# Connectors.net
KiCad netlist of a schematic drawn in Altium Designer
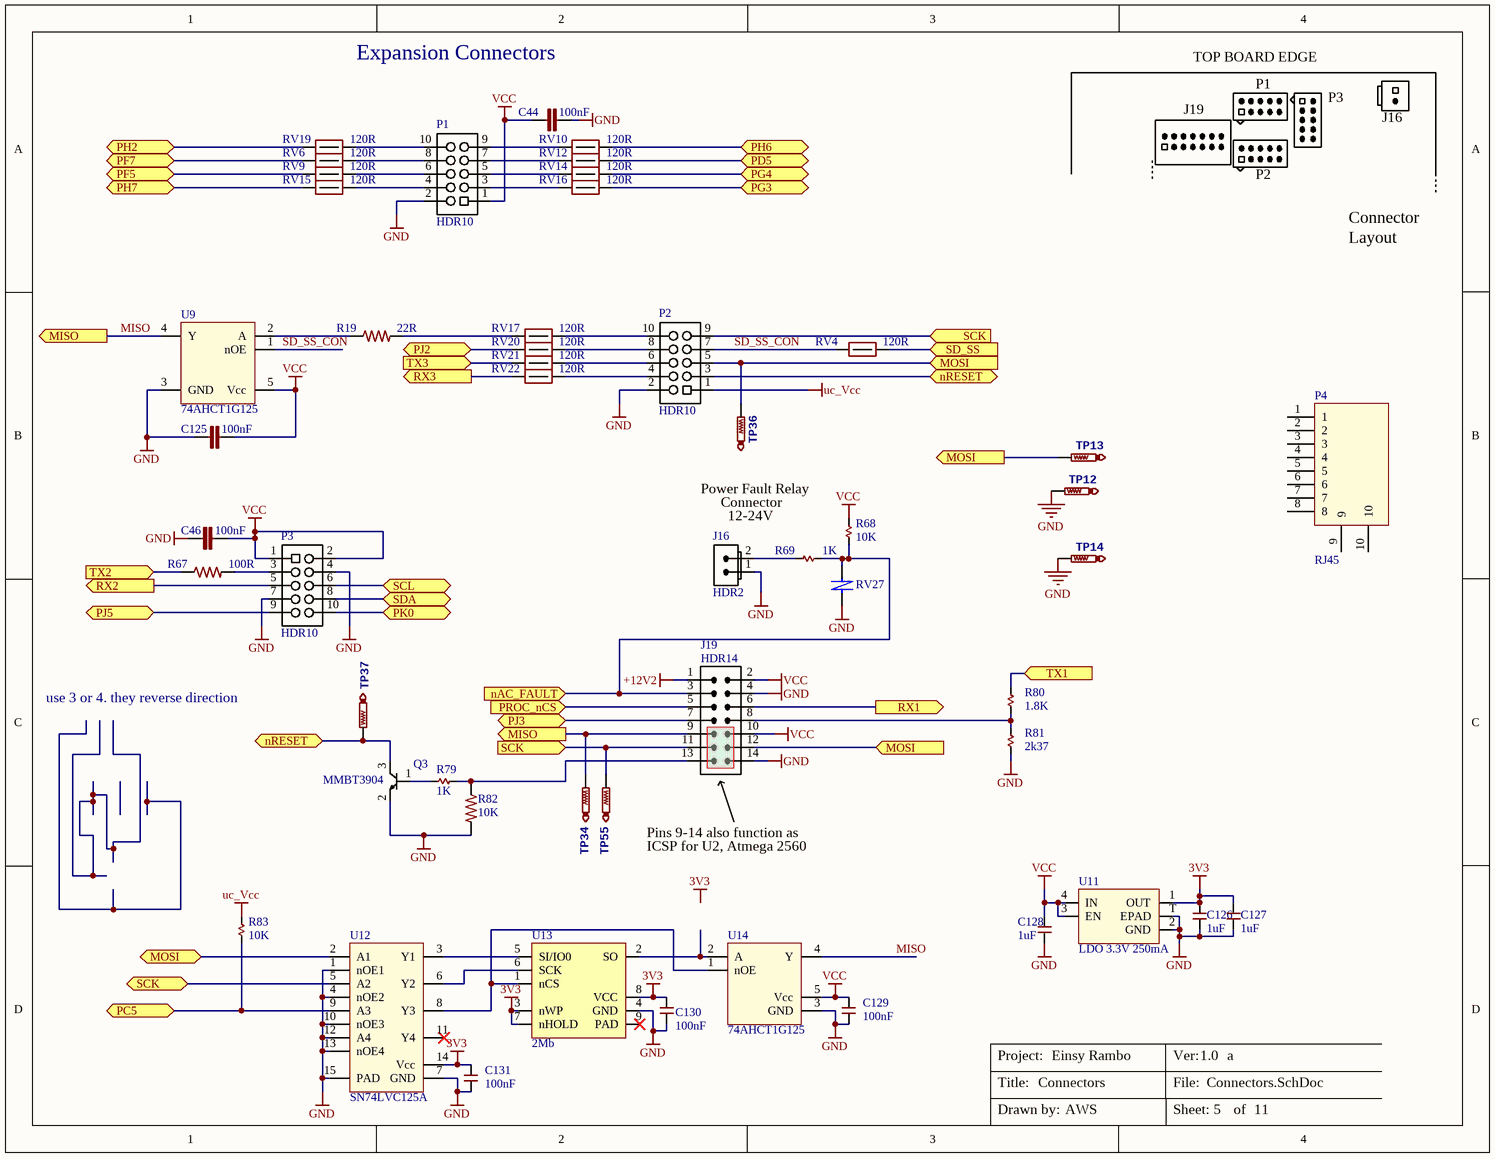
[diagram p0: Connectors.SchDoc]

(export (version "E")
  (design (tool "Eeschema 10.0.6"))
  (components
    (comp (ref "C44")
      (value "100nF")
      (footprint "C0402")
      (description "CAP CER 0402 100nF 16V 10% X7R")
      (fields (field (name "MANUFACTURER") "Murata") (field (name "TOLERANCE") "+/- 10%"))
      (libsource (lib "3Delight") (part "GRM155R71C104KA88D"))
    )
    (comp (ref "C46")
      (value "100nF")
      (footprint "C0402")
      (description "CAP CER 0402 100nF 16V 10% X7R")
      (fields (field (name "MANUFACTURER") "Murata") (field (name "TOLERANCE") "+/- 10%"))
      (libsource (lib "3Delight") (part "GRM155R71C104KA88D"))
    )
    (comp (ref "C125")
      (value "100nF")
      (footprint "C0402")
      (description "CAP CER 0402 100nF 16V 10% X7R")
      (fields (field (name "MANUFACTURER") "Murata") (field (name "TOLERANCE") "+/- 10%"))
      (libsource (lib "3Delight") (part "GRM155R71C104KA88D"))
    )
    (comp (ref "C126")
      (value "1uF")
      (footprint "C0402")
      (description "CAP CER 0402 1uF 6.3V 10% X5R")
      (fields (field (name "MANUFACTURER") "Murata") (field (name "PART") "1uF 6.3V X5R 0402"))
      (libsource (lib "Capacitors") (part "1uF 0402 6.3V X5R"))
    )
    (comp (ref "C127")
      (value "1uF")
      (footprint "C0402")
      (description "CAP CER 0402 1uF 6.3V 10% X5R")
      (fields (field (name "MANUFACTURER") "Murata") (field (name "PART") "1uF 6.3V X5R 0402"))
      (libsource (lib "Capacitors") (part "1uF 0402 6.3V X5R"))
    )
    (comp (ref "C128")
      (value "1uF")
      (footprint "C0402")
      (description "CAP CER 0402 1uF 6.3V 10% X5R")
      (fields (field (name "MANUFACTURER") "Murata") (field (name "PART") "1uF 6.3V X5R 0402"))
      (libsource (lib "Capacitors") (part "1uF 0402 6.3V X5R"))
    )
    (comp (ref "C129")
      (value "100nF")
      (footprint "C0402")
      (description "CAP CER 0402 100nF 16V 10% X7R")
      (fields (field (name "MANUFACTURER") "Murata") (field (name "PART") "0.1uF 16V X7R 0402"))
      (libsource (lib "Capacitors") (part "100nF 0402 16V X7R"))
    )
    (comp (ref "C130")
      (value "100nF")
      (footprint "C0402")
      (description "CAP CER 0402 100nF 16V 10% X7R")
      (fields (field (name "MANUFACTURER") "Murata") (field (name "PART") "0.1uF 16V X7R 0402"))
      (libsource (lib "Capacitors") (part "100nF 0402 16V X7R"))
    )
    (comp (ref "C131")
      (value "100nF")
      (footprint "C0402")
      (description "CAP CER 0402 100nF 16V 10% X7R")
      (fields (field (name "MANUFACTURER") "Murata") (field (name "PART") "0.1uF 16V X7R 0402"))
      (libsource (lib "Capacitors") (part "100nF 0402 16V X7R"))
    )
    (comp (ref "J16")
      (value "HDR2")
      (footprint "70543-02")
      (description "Connector 2pos")
      (fields (field (name "MANUFACTURER") "Molex") (field (name "PART") "10 Pin Conn"))
      (libsource (lib "Archim_0.4") (part "CONN 2PIN VERT 0.1{dblquote} SHRD LOCKING"))
    )
    (comp (ref "J19")
      (value "HDR14")
      (footprint "HDR2x7_SMT_BOT_ENTRY")
      (description "CONN RCPT DUAL ENTRY 14POS .100\"")
      (fields (field (name "MANUFACTURER") "TE Connectivity") (field (name "TOLERANCE") "-NA-"))
      (libsource (lib "Connectors") (part "CONN 14PIN 0.1{dblquote} FEMALE 2-ROW SMT BOT-ENTRY"))
    )
    (comp (ref "P1")
      (value "HDR10")
      (footprint "HDR2X5 IDC")
      (description "CONN HEADER VERT 10POS GOLD")
      (fields (field (name "MANUFACTURER") "On Shore") (field (name "TOLERANCE") "-NA-"))
      (libsource (lib "Connectors") (part "Header 10PIN 2ROW T-HOLE VERT SHROUDED"))
    )
    (comp (ref "P2")
      (value "HDR10")
      (footprint "HDR2X5 IDC")
      (description "CONN HEADER VERT 10POS GOLD")
      (fields (field (name "MANUFACTURER") "On Shore") (field (name "TOLERANCE") "-NA-"))
      (libsource (lib "Connectors") (part "Header 10PIN 2ROW T-HOLE VERT SHROUDED"))
    )
    (comp (ref "P3")
      (value "HDR10")
      (footprint "HDR2X5 IDC THIEVING")
      (description "CONN HEADER VERT 10POS GOLD")
      (fields (field (name "MANUFACTURER") "On Shore") (field (name "TOLERANCE") "-NA-"))
      (libsource (lib "") (part "Header 10PIN 2ROW T-HOLE VERT SHROUDED_1"))
    )
    (comp (ref "P4")
      (value "RJ45")
      (footprint "RJ45 SMT")
      (description "RJCSE538001")
      (libsource (lib "3Delight") (part "RJ45 SMT"))
    )
    (comp (ref "Q3")
      (value "MMBT3904")
      (footprint "SOT523 SMALL")
      (description "TRANS NPN 60V 0.2A SOT523")
      (fields
        (field (name "MANUFACTURER") "Diodes Incorporated")
        (field (name "PART") "TRANS NPN 40V 0.2A SOT523")
      )
      (libsource (lib "Transistors") (part "MMBT3904_SOT523"))
    )
    (comp (ref "R19")
      (value "22R")
      (footprint "R0402")
      (description "RES 0402 22r 62.5mW 1%")
      (fields (field (name "MANUFACTURER") "Yageo") (field (name "TOLERANCE") "+/- 1%"))
      (libsource (lib "3Delight") (part "RC0402FR-0722RL"))
    )
    (comp (ref "R67")
      (value "100R")
      (footprint "R0402")
      (description "RES SMD 100 OHM 1% 1/16W 0402")
      (fields (field (name "MANUFACTURER") "Yageo") (field (name "PART") "100R 1% 0402"))
      (libsource (lib "Archim") (part "RES 100R 0402 1%"))
    )
    (comp (ref "R68")
      (value "10K")
      (footprint "R0402")
      (description "RES SMD 10K OHM 1% 1/16W 0402")
      (fields (field (name "MANUFACTURER") "Yageo") (field (name "PART") "10k 1% 0402"))
      (libsource (lib "Resistors") (part "10k 1% 0402"))
    )
    (comp (ref "R69")
      (value "1K")
      (footprint "R0402")
      (description "RES SMD 1K OHM 1% 1/16W 0402")
      (fields (field (name "MANUFACTURER") "Yageo") (field (name "PART") "1k"))
      (libsource (lib "3Delight") (part "RC0402FR-071KL"))
    )
    (comp (ref "R79")
      (value "1K")
      (footprint "R0402")
      (description "RES SMD 1K OHM 1% 1/16W 0402")
      (fields (field (name "MANUFACTURER") "Yageo") (field (name "PART") "1k"))
      (libsource (lib "3Delight") (part "RC0402FR-071KL"))
    )
    (comp (ref "R80")
      (value "1.8K")
      (footprint "R0402")
      (description "RES SMD 1.8K OHM 1% 1/16W 0402")
      (fields (field (name "MANUFACTURER") "Yageo") (field (name "PART") "1.8k"))
      (libsource (lib "3Delight") (part "RC0402FR-071K8L"))
    )
    (comp (ref "R81")
      (value "2k37")
      (footprint "R0402")
      (description "RES SMD 2.37K OHM 1% 1/16W 0402")
      (fields (field (name "MANUFACTURER") "Yageo") (field (name "PART") "2.37k"))
      (libsource (lib "3Delight") (part "RC0402FR-072K37L"))
    )
    (comp (ref "R82")
      (value "10K")
      (footprint "R0402")
      (description "RES SMD 10K OHM 1% 1/16W 0402")
      (fields (field (name "MANUFACTURER") "Yageo") (field (name "PART") "10k 1% 0402"))
      (libsource (lib "3Delight") (part "RC0402FR-0710KP"))
    )
    (comp (ref "R83")
      (value "10K")
      (footprint "R0402")
      (description "RES SMD 10K OHM 1% 1/16W 0402")
      (fields (field (name "MANUFACTURER") "Yageo") (field (name "PART") "10k 1% 0402"))
      (libsource (lib "Resistors") (part "10k 1% 0402"))
    )
    (comp (ref "RV4")
      (value "120R")
      (footprint "R0402")
      (description "FERRITE BEAD 120 OHM 0402 1LN")
      (fields (field (name "MANUFACTURER") "Taiyo Yuden") (field (name "PART") "FERRITE 120R 1A 0402"))
      (libsource (lib "Inductors") (part "FERRITE 120R 1A 0402"))
    )
    (comp (ref "RV6")
      (value "120R")
      (footprint "R0402")
      (description "FERRITE BEAD 120 OHM 0402 1LN")
      (fields (field (name "MANUFACTURER") "Taiyo Yuden") (field (name "PART") "FERRITE 120R 1A 0402"))
      (libsource (lib "Inductors") (part "FERRITE 120R 1A 0402"))
    )
    (comp (ref "RV9")
      (value "120R")
      (footprint "R0402")
      (description "FERRITE BEAD 120 OHM 0402 1LN")
      (fields (field (name "MANUFACTURER") "Taiyo Yuden") (field (name "PART") "FERRITE 120R 1A 0402"))
      (libsource (lib "Inductors") (part "FERRITE 120R 1A 0402"))
    )
    (comp (ref "RV10")
      (value "120R")
      (footprint "R0402")
      (description "FERRITE BEAD 120 OHM 0402 1LN")
      (fields (field (name "MANUFACTURER") "Taiyo Yuden") (field (name "PART") "FERRITE 120R 1A 0402"))
      (libsource (lib "Inductors") (part "FERRITE 120R 1A 0402"))
    )
    (comp (ref "RV12")
      (value "120R")
      (footprint "R0402")
      (description "FERRITE BEAD 120 OHM 0402 1LN")
      (fields (field (name "MANUFACTURER") "Taiyo Yuden") (field (name "PART") "FERRITE 120R 1A 0402"))
      (libsource (lib "Inductors") (part "FERRITE 120R 1A 0402"))
    )
    (comp (ref "RV14")
      (value "120R")
      (footprint "R0402")
      (description "FERRITE BEAD 120 OHM 0402 1LN")
      (fields (field (name "MANUFACTURER") "Taiyo Yuden") (field (name "PART") "FERRITE 120R 1A 0402"))
      (libsource (lib "Inductors") (part "FERRITE 120R 1A 0402"))
    )
    (comp (ref "RV15")
      (value "120R")
      (footprint "R0402")
      (description "FERRITE BEAD 120 OHM 0402 1LN")
      (fields (field (name "MANUFACTURER") "Taiyo Yuden") (field (name "PART") "FERRITE 120R 1A 0402"))
      (libsource (lib "Inductors") (part "FERRITE 120R 1A 0402"))
    )
    (comp (ref "RV16")
      (value "120R")
      (footprint "R0402")
      (description "FERRITE BEAD 120 OHM 0402 1LN")
      (fields (field (name "MANUFACTURER") "Taiyo Yuden") (field (name "PART") "FERRITE 120R 1A 0402"))
      (libsource (lib "Inductors") (part "FERRITE 120R 1A 0402"))
    )
    (comp (ref "RV17")
      (value "120R")
      (footprint "R0402")
      (description "FERRITE BEAD 120 OHM 0402 1LN")
      (fields (field (name "MANUFACTURER") "Taiyo Yuden") (field (name "PART") "FERRITE 120R 1A 0402"))
      (libsource (lib "Inductors") (part "FERRITE 120R 1A 0402"))
    )
    (comp (ref "RV19")
      (value "120R")
      (footprint "R0402")
      (description "FERRITE BEAD 120 OHM 0402 1LN")
      (fields (field (name "MANUFACTURER") "Taiyo Yuden") (field (name "PART") "FERRITE 120R 1A 0402"))
      (libsource (lib "Inductors") (part "FERRITE 120R 1A 0402"))
    )
    (comp (ref "RV20")
      (value "120R")
      (footprint "R0402")
      (description "FERRITE BEAD 120 OHM 0402 1LN")
      (fields (field (name "MANUFACTURER") "Taiyo Yuden") (field (name "PART") "FERRITE 120R 1A 0402"))
      (libsource (lib "Inductors") (part "FERRITE 120R 1A 0402"))
    )
    (comp (ref "RV21")
      (value "120R")
      (footprint "R0402")
      (description "FERRITE BEAD 120 OHM 0402 1LN")
      (fields (field (name "MANUFACTURER") "Taiyo Yuden") (field (name "PART") "FERRITE 120R 1A 0402"))
      (libsource (lib "Inductors") (part "FERRITE 120R 1A 0402"))
    )
    (comp (ref "RV22")
      (value "120R")
      (footprint "R0402")
      (description "FERRITE BEAD 120 OHM 0402 1LN")
      (fields (field (name "MANUFACTURER") "Taiyo Yuden") (field (name "PART") "FERRITE 120R 1A 0402"))
      (libsource (lib "Inductors") (part "FERRITE 120R 1A 0402"))
    )
    (comp (ref "RV27")
      (value "VRS0402SR55R101N")
      (footprint "C0402")
      (description "Multi-Layer Varistor")
      (fields (field (name "MANUFACTURER") "Yageo") (field (name "PART") "12V"))
      (libsource (lib "3Delight") (part "VRS0402SR55R101N"))
    )
    (comp (ref "TP12")
      (value "TestPoint")
      (footprint "TP1-27")
      (description "Test Point")
      (libsource (lib "3Delight") (part "TestPoint"))
    )
    (comp (ref "TP13")
      (value "TestPoint")
      (footprint "TP1-27")
      (description "Test Point")
      (libsource (lib "3Delight") (part "TestPoint"))
    )
    (comp (ref "TP14")
      (value "TestPoint")
      (footprint "TP1-27")
      (description "Test Point")
      (libsource (lib "3Delight") (part "TestPoint"))
    )
    (comp (ref "TP34")
      (value "TestPoint")
      (footprint "TP1-27")
      (description "Test Point")
      (libsource (lib "") (part "TestPoint_1"))
    )
    (comp (ref "TP36")
      (value "TestPoint")
      (footprint "TP1-27")
      (description "Test Point")
      (libsource (lib "") (part "TestPoint_1"))
    )
    (comp (ref "TP37")
      (value "TestPoint")
      (footprint "TP1-27")
      (description "Test Point")
      (libsource (lib "") (part "TestPoint_2"))
    )
    (comp (ref "TP55")
      (value "TestPoint")
      (footprint "TP1-27")
      (description "Test Point")
      (libsource (lib "") (part "TestPoint_1"))
    )
    (comp (ref "U9")
      (value "74AHCT1G125")
      (footprint "SOTFL50P160X60-5L")
      (description "IC BUS BUFF TRI-ST N-INV  SOT-553")
      (fields (field (name "TOLERANCE") "-NA-") (field (name "MANUFACTURER") "TI"))
      (libsource (lib "ICs-Logic") (part "SN74AHCT1G125DRLR"))
    )
    (comp (ref "U11")
      (value "LDO 3.3V 250mA")
      (footprint "XDFN4 1X1")
      (description "IC REG LINEAR 3.3V 250MA 4XDFN")
      (fields (field (name "MANUFACTURER") "On Semi") (field (name "TOLERANCE") "-NA-"))
      (libsource (lib "ICs-Power") (part "LDO 3.3V 250mA"))
    )
    (comp (ref "U12")
      (value "SN74LVC125A")
      (footprint "PVQFN14_3.5X3.5")
      (description "IC BUS BUFF TRI-ST QD 14VQFN")
      (fields (field (name "TOLERANCE") "-NA-") (field (name "MANUFACTURER") "TI"))
      (libsource (lib "ICs-Logic") (part "SN74LVC125A"))
    )
    (comp (ref "U13")
      (value "2Mb")
      (footprint "USON8 2X3")
      (description "IC FLASH 2MBIT 104MHZ 8USON")
      (fields (field (name "MANUFACTURER") "Winbond") (field (name "TOLERANCE") "-NA-"))
      (libsource (lib "ICs-uC") (part "W25X20CL"))
    )
    (comp (ref "U14")
      (value "74AHCT1G125")
      (footprint "SOTFL50P160X60-5L")
      (description "IC BUS BUFF TRI-ST N-INV  SOT-553")
      (fields (field (name "TOLERANCE") "-NA-") (field (name "MANUFACTURER") "TI"))
      (libsource (lib "") (part "SN74AHCT1G125DRLR_1"))
    )
  )
  (nets
    (net (code "1") (name "+12V2") (class "Default")
      (node (ref "J19") (pin "1") (pinfunction "S_1") (pintype "passive"))
    )
    (net (code "2") (name "/MISO") (class "Default")
      (node (ref "J19") (pin "9") (pinfunction "S_9") (pintype "passive"))
      (node (ref "TP34") (pin "TP") (pinfunction "TP_TP") (pintype "passive"))
      (node (ref "U14") (pin "4") (pinfunction "Y_4") (pintype "passive"))
      (node (ref "U9") (pin "4") (pinfunction "Y_4") (pintype "passive"))
    )
    (net (code "3") (name "/MOSI") (class "Default")
      (node (ref "J19") (pin "12") (pinfunction "S_12") (pintype "passive"))
      (node (ref "P2") (pin "5") (pinfunction "5_5") (pintype "passive"))
      (node (ref "TP13") (pin "TP") (pinfunction "TP_TP") (pintype "passive"))
      (node (ref "TP36") (pin "TP") (pinfunction "TP_TP") (pintype "passive"))
      (node (ref "U12") (pin "2") (pinfunction "A1_2") (pintype "passive"))
    )
    (net (code "4") (name "/PC5") (class "Default")
      (node (ref "R83") (pin "2") (pinfunction "2_2") (pintype "passive"))
      (node (ref "U12") (pin "9") (pinfunction "A3_9") (pintype "passive"))
    )
    (net (code "5") (name "/PD5") (class "Default")
      (node (ref "RV12") (pin "2") (pinfunction "2_2") (pintype "passive"))
    )
    (net (code "6") (name "/PF5") (class "Default")
      (node (ref "RV9") (pin "1") (pinfunction "1_1") (pintype "passive"))
    )
    (net (code "7") (name "/PF7") (class "Default")
      (node (ref "RV6") (pin "1") (pinfunction "1_1") (pintype "passive"))
    )
    (net (code "8") (name "/PG3") (class "Default")
      (node (ref "RV16") (pin "2") (pinfunction "2_2") (pintype "passive"))
    )
    (net (code "9") (name "/PG4") (class "Default")
      (node (ref "RV14") (pin "2") (pinfunction "2_2") (pintype "passive"))
    )
    (net (code "10") (name "/PH2") (class "Default")
      (node (ref "RV19") (pin "1") (pinfunction "1_1") (pintype "passive"))
    )
    (net (code "11") (name "/PH6") (class "Default")
      (node (ref "RV10") (pin "2") (pinfunction "2_2") (pintype "passive"))
    )
    (net (code "12") (name "/PH7") (class "Default")
      (node (ref "RV15") (pin "1") (pinfunction "1_1") (pintype "passive"))
    )
    (net (code "13") (name "/PJ2") (class "Default")
      (node (ref "RV20") (pin "1") (pinfunction "1_1") (pintype "passive"))
    )
    (net (code "14") (name "/PJ3") (class "Default")
      (node (ref "J19") (pin "7") (pinfunction "S_7") (pintype "passive"))
    )
    (net (code "15") (name "/PJ5") (class "Default")
      (node (ref "P3") (pin "9") (pinfunction "9_9") (pintype "passive"))
    )
    (net (code "16") (name "/PK0") (class "Default")
      (node (ref "P3") (pin "10") (pinfunction "10_10") (pintype "passive"))
    )
    (net (code "17") (name "/PROC_nCS") (class "Default")
      (node (ref "J19") (pin "5") (pinfunction "S_5") (pintype "passive"))
    )
    (net (code "18") (name "/RX1") (class "Default")
      (node (ref "J19") (pin "6") (pinfunction "S_6") (pintype "passive"))
    )
    (net (code "19") (name "/RX2") (class "Default")
      (node (ref "P3") (pin "5") (pinfunction "5_5") (pintype "passive"))
    )
    (net (code "20") (name "/RX3") (class "Default")
      (node (ref "RV22") (pin "1") (pinfunction "1_1") (pintype "passive"))
    )
    (net (code "21") (name "/SCK") (class "Default")
      (node (ref "J19") (pin "11") (pinfunction "S_11") (pintype "passive"))
      (node (ref "P2") (pin "9") (pinfunction "9_9") (pintype "passive"))
      (node (ref "TP55") (pin "TP") (pinfunction "TP_TP") (pintype "passive"))
      (node (ref "U12") (pin "5") (pinfunction "A2_5") (pintype "passive"))
    )
    (net (code "22") (name "/SCL") (class "Default")
      (node (ref "P3") (pin "6") (pinfunction "6_6") (pintype "passive"))
    )
    (net (code "23") (name "/SDA") (class "Default")
      (node (ref "P3") (pin "8") (pinfunction "8_8") (pintype "passive"))
    )
    (net (code "24") (name "/SD_SS") (class "Default")
      (node (ref "RV4") (pin "2") (pinfunction "2_2") (pintype "passive"))
    )
    (net (code "25") (name "/SD_SS_CON") (class "Default")
      (node (ref "P2") (pin "7") (pinfunction "7_7") (pintype "passive"))
      (node (ref "RV4") (pin "1") (pinfunction "1_1") (pintype "passive"))
      (node (ref "U9") (pin "1") (pinfunction "nOE_1") (pintype "passive"))
    )
    (net (code "26") (name "/TX1") (class "Default")
      (node (ref "R80") (pin "1") (pinfunction "1_1") (pintype "passive"))
    )
    (net (code "27") (name "/TX2") (class "Default")
      (node (ref "R67") (pin "1") (pinfunction "1_1") (pintype "passive"))
    )
    (net (code "28") (name "/TX3") (class "Default")
      (node (ref "RV21") (pin "1") (pinfunction "1_1") (pintype "passive"))
    )
    (net (code "29") (name "/nAC_FAULT") (class "Default")
      (node (ref "J19") (pin "3") (pinfunction "S_3") (pintype "passive"))
      (node (ref "R68") (pin "1") (pinfunction "1_1") (pintype "passive"))
      (node (ref "R69") (pin "2") (pinfunction "2_2") (pintype "passive"))
      (node (ref "RV27") (pin "2") (pinfunction "2_2") (pintype "passive"))
    )
    (net (code "30") (name "/nRESET") (class "Default")
      (node (ref "P2") (pin "3") (pinfunction "3_3") (pintype "passive"))
      (node (ref "Q3") (pin "3") (pinfunction "C_3") (pintype "power_in"))
      (node (ref "TP37") (pin "TP") (pinfunction "TP_TP") (pintype "passive"))
    )
    (net (code "31") (name "3V3") (class "Default")
      (node (ref "C126") (pin "2") (pinfunction "2_2") (pintype "passive"))
      (node (ref "C127") (pin "2") (pinfunction "2_2") (pintype "passive"))
      (node (ref "C130") (pin "2") (pinfunction "2_2") (pintype "passive"))
      (node (ref "C131") (pin "1") (pinfunction "1_1") (pintype "passive"))
      (node (ref "U11") (pin "1") (pinfunction "OUT_1") (pintype "power_in"))
      (node (ref "U12") (pin "14") (pinfunction "Vcc_14") (pintype "passive"))
      (node (ref "U13") (pin "3") (pinfunction "nWP_3") (pintype "passive"))
      (node (ref "U13") (pin "7") (pinfunction "nHOLD_7") (pintype "passive"))
      (node (ref "U13") (pin "8") (pinfunction "VCC_8") (pintype "passive"))
    )
    (net (code "32") (name "GND") (class "Default")
      (node (ref "C125") (pin "1") (pinfunction "1_1") (pintype "passive"))
      (node (ref "C126") (pin "1") (pinfunction "1_1") (pintype "passive"))
      (node (ref "C127") (pin "1") (pinfunction "1_1") (pintype "passive"))
      (node (ref "C128") (pin "1") (pinfunction "1_1") (pintype "passive"))
      (node (ref "C129") (pin "1") (pinfunction "1_1") (pintype "passive"))
      (node (ref "C130") (pin "1") (pinfunction "1_1") (pintype "passive"))
      (node (ref "C131") (pin "2") (pinfunction "2_2") (pintype "passive"))
      (node (ref "C44") (pin "2") (pinfunction "2_2") (pintype "passive"))
      (node (ref "C46") (pin "1") (pinfunction "1_1") (pintype "passive"))
      (node (ref "J16") (pin "1") (pinfunction "S_1") (pintype "passive"))
      (node (ref "J19") (pin "14") (pinfunction "S_14") (pintype "passive"))
      (node (ref "J19") (pin "4") (pinfunction "S_4") (pintype "passive"))
      (node (ref "P1") (pin "2") (pinfunction "2_2") (pintype "passive"))
      (node (ref "P2") (pin "2") (pinfunction "2_2") (pintype "passive"))
      (node (ref "P3") (pin "4") (pinfunction "4_4") (pintype "passive"))
      (node (ref "P3") (pin "7") (pinfunction "7_7") (pintype "passive"))
      (node (ref "Q3") (pin "2") (pinfunction "E_2") (pintype "power_in"))
      (node (ref "R81") (pin "2") (pinfunction "2_2") (pintype "passive"))
      (node (ref "R82") (pin "2") (pinfunction "2_2") (pintype "passive"))
      (node (ref "RV27") (pin "1") (pinfunction "1_1") (pintype "passive"))
      (node (ref "TP12") (pin "TP") (pinfunction "TP_TP") (pintype "passive"))
      (node (ref "TP14") (pin "TP") (pinfunction "TP_TP") (pintype "passive"))
      (node (ref "U11") (pin "2") (pinfunction "GND_2") (pintype "power_in"))
      (node (ref "U11") (pin "T") (pinfunction "EPAD_T") (pintype "power_in"))
      (node (ref "U12") (pin "1") (pinfunction "nOE1_1") (pintype "passive"))
      (node (ref "U12") (pin "10") (pinfunction "nOE3_10") (pintype "passive"))
      (node (ref "U12") (pin "12") (pinfunction "A4_12") (pintype "passive"))
      (node (ref "U12") (pin "13") (pinfunction "nOE4_13") (pintype "passive"))
      (node (ref "U12") (pin "15") (pinfunction "PAD_15") (pintype "passive"))
      (node (ref "U12") (pin "4") (pinfunction "nOE2_4") (pintype "passive"))
      (node (ref "U12") (pin "7") (pinfunction "GND_7") (pintype "passive"))
      (node (ref "U13") (pin "4") (pinfunction "GND_4") (pintype "passive"))
      (node (ref "U14") (pin "3") (pinfunction "GND_3") (pintype "passive"))
      (node (ref "U9") (pin "3") (pinfunction "GND_3") (pintype "passive"))
    )
    (net (code "33") (name "Net-(J16-S-Pad2)") (class "Default")
      (node (ref "J16") (pin "2") (pinfunction "S_2") (pintype "passive"))
      (node (ref "R69") (pin "1") (pinfunction "1_1") (pintype "passive"))
    )
    (net (code "34") (name "Net-(J19-S-Pad8)") (class "Default")
      (node (ref "J19") (pin "8") (pinfunction "S_8") (pintype "passive"))
      (node (ref "R80") (pin "2") (pinfunction "2_2") (pintype "passive"))
      (node (ref "R81") (pin "1") (pinfunction "1_1") (pintype "passive"))
    )
    (net (code "35") (name "Net-(J19-S-Pad13)") (class "Default")
      (node (ref "J19") (pin "13") (pinfunction "S_13") (pintype "passive"))
      (node (ref "R79") (pin "1") (pinfunction "1_1") (pintype "passive"))
      (node (ref "R82") (pin "1") (pinfunction "1_1") (pintype "passive"))
    )
    (net (code "36") (name "Net-(P1-Pad3)") (class "Default")
      (node (ref "P1") (pin "3") (pinfunction "3_3") (pintype "passive"))
      (node (ref "RV16") (pin "1") (pinfunction "1_1") (pintype "passive"))
    )
    (net (code "37") (name "Net-(P1-Pad4)") (class "Default")
      (node (ref "P1") (pin "4") (pinfunction "4_4") (pintype "passive"))
      (node (ref "RV15") (pin "2") (pinfunction "2_2") (pintype "passive"))
    )
    (net (code "38") (name "Net-(P1-Pad5)") (class "Default")
      (node (ref "P1") (pin "5") (pinfunction "5_5") (pintype "passive"))
      (node (ref "RV14") (pin "1") (pinfunction "1_1") (pintype "passive"))
    )
    (net (code "39") (name "Net-(P1-Pad6)") (class "Default")
      (node (ref "P1") (pin "6") (pinfunction "6_6") (pintype "passive"))
      (node (ref "RV9") (pin "2") (pinfunction "2_2") (pintype "passive"))
    )
    (net (code "40") (name "Net-(P1-Pad7)") (class "Default")
      (node (ref "P1") (pin "7") (pinfunction "7_7") (pintype "passive"))
      (node (ref "RV12") (pin "1") (pinfunction "1_1") (pintype "passive"))
    )
    (net (code "41") (name "Net-(P1-Pad8)") (class "Default")
      (node (ref "P1") (pin "8") (pinfunction "8_8") (pintype "passive"))
      (node (ref "RV6") (pin "2") (pinfunction "2_2") (pintype "passive"))
    )
    (net (code "42") (name "Net-(P1-Pad9)") (class "Default")
      (node (ref "P1") (pin "9") (pinfunction "9_9") (pintype "passive"))
      (node (ref "RV10") (pin "1") (pinfunction "1_1") (pintype "passive"))
    )
    (net (code "43") (name "Net-(P1-Pad10)") (class "Default")
      (node (ref "P1") (pin "10") (pinfunction "10_10") (pintype "passive"))
      (node (ref "RV19") (pin "2") (pinfunction "2_2") (pintype "passive"))
    )
    (net (code "44") (name "Net-(P2-Pad4)") (class "Default")
      (node (ref "P2") (pin "4") (pinfunction "4_4") (pintype "passive"))
      (node (ref "RV22") (pin "2") (pinfunction "2_2") (pintype "passive"))
    )
    (net (code "45") (name "Net-(P2-Pad6)") (class "Default")
      (node (ref "P2") (pin "6") (pinfunction "6_6") (pintype "passive"))
      (node (ref "RV21") (pin "2") (pinfunction "2_2") (pintype "passive"))
    )
    (net (code "46") (name "Net-(P2-Pad8)") (class "Default")
      (node (ref "P2") (pin "8") (pinfunction "8_8") (pintype "passive"))
      (node (ref "RV20") (pin "2") (pinfunction "2_2") (pintype "passive"))
    )
    (net (code "47") (name "Net-(P2-Pad10)") (class "Default")
      (node (ref "P2") (pin "10") (pinfunction "10_10") (pintype "passive"))
      (node (ref "RV17") (pin "2") (pinfunction "2_2") (pintype "passive"))
    )
    (net (code "48") (name "Net-(P3-Pad3)") (class "Default")
      (node (ref "P3") (pin "3") (pinfunction "3_3") (pintype "passive"))
      (node (ref "R67") (pin "2") (pinfunction "2_2") (pintype "passive"))
    )
    (net (code "49") (name "Net-(Q3-B)") (class "Default")
      (node (ref "Q3") (pin "1") (pinfunction "B_1") (pintype "power_in"))
      (node (ref "R79") (pin "2") (pinfunction "2_2") (pintype "passive"))
    )
    (net (code "50") (name "Net-(R19-Pad2)") (class "Default")
      (node (ref "R19") (pin "2") (pinfunction "2_2") (pintype "passive"))
      (node (ref "RV17") (pin "1") (pinfunction "1_1") (pintype "passive"))
    )
    (net (code "51") (name "Net-(U9-A)") (class "Default")
      (node (ref "R19") (pin "1") (pinfunction "1_1") (pintype "passive"))
      (node (ref "U9") (pin "2") (pinfunction "A_2") (pintype "passive"))
    )
    (net (code "52") (name "Net-(U12-Y1)") (class "Default")
      (node (ref "U12") (pin "3") (pinfunction "Y1_3") (pintype "passive"))
      (node (ref "U13") (pin "5") (pinfunction "SI/IO0_5") (pintype "passive"))
    )
    (net (code "53") (name "Net-(U12-Y2)") (class "Default")
      (node (ref "U12") (pin "6") (pinfunction "Y2_6") (pintype "passive"))
      (node (ref "U13") (pin "6") (pinfunction "SCK_6") (pintype "passive"))
    )
    (net (code "54") (name "Net-(U12-Y3)") (class "Default")
      (node (ref "U12") (pin "8") (pinfunction "Y3_8") (pintype "passive"))
      (node (ref "U13") (pin "1") (pinfunction "nCS_1") (pintype "passive"))
      (node (ref "U14") (pin "1") (pinfunction "nOE_1") (pintype "passive"))
    )
    (net (code "55") (name "Net-(U13-SO)") (class "Default")
      (node (ref "U13") (pin "2") (pinfunction "SO_2") (pintype "passive"))
      (node (ref "U14") (pin "2") (pinfunction "A_2") (pintype "passive"))
    )
    (net (code "56") (name "VCC") (class "Default")
      (node (ref "C125") (pin "2") (pinfunction "2_2") (pintype "passive"))
      (node (ref "C128") (pin "2") (pinfunction "2_2") (pintype "passive"))
      (node (ref "C129") (pin "2") (pinfunction "2_2") (pintype "passive"))
      (node (ref "C44") (pin "1") (pinfunction "1_1") (pintype "passive"))
      (node (ref "C46") (pin "2") (pinfunction "2_2") (pintype "passive"))
      (node (ref "J19") (pin "10") (pinfunction "S_10") (pintype "passive"))
      (node (ref "J19") (pin "2") (pinfunction "S_2") (pintype "passive"))
      (node (ref "P1") (pin "1") (pinfunction "1_1") (pintype "passive"))
      (node (ref "P3") (pin "1") (pinfunction "1_1") (pintype "passive"))
      (node (ref "P3") (pin "2") (pinfunction "2_2") (pintype "passive"))
      (node (ref "R68") (pin "2") (pinfunction "2_2") (pintype "passive"))
      (node (ref "U11") (pin "3") (pinfunction "EN_3") (pintype "power_in"))
      (node (ref "U11") (pin "4") (pinfunction "IN_4") (pintype "power_in"))
      (node (ref "U14") (pin "5") (pinfunction "Vcc_5") (pintype "passive"))
      (node (ref "U9") (pin "5") (pinfunction "Vcc_5") (pintype "passive"))
    )
    (net (code "57") (name "uc_Vcc") (class "Default")
      (node (ref "P2") (pin "1") (pinfunction "1_1") (pintype "passive"))
      (node (ref "R83") (pin "1") (pinfunction "1_1") (pintype "passive"))
    )
    (net (code "58") (name "unconnected-(P4-Pad1)") (class "Default")
      (node (ref "P4") (pin "1") (pinfunction "1_1") (pintype "passive"))
    )
    (net (code "59") (name "unconnected-(P4-Pad2)") (class "Default")
      (node (ref "P4") (pin "2") (pinfunction "2_2") (pintype "passive"))
    )
    (net (code "60") (name "unconnected-(P4-Pad3)") (class "Default")
      (node (ref "P4") (pin "3") (pinfunction "3_3") (pintype "passive"))
    )
    (net (code "61") (name "unconnected-(P4-Pad4)") (class "Default")
      (node (ref "P4") (pin "4") (pinfunction "4_4") (pintype "passive"))
    )
    (net (code "62") (name "unconnected-(P4-Pad5)") (class "Default")
      (node (ref "P4") (pin "5") (pinfunction "5_5") (pintype "passive"))
    )
    (net (code "63") (name "unconnected-(P4-Pad6)") (class "Default")
      (node (ref "P4") (pin "6") (pinfunction "6_6") (pintype "passive"))
    )
    (net (code "64") (name "unconnected-(P4-Pad7)") (class "Default")
      (node (ref "P4") (pin "7") (pinfunction "7_7") (pintype "passive"))
    )
    (net (code "65") (name "unconnected-(P4-Pad8)") (class "Default")
      (node (ref "P4") (pin "8") (pinfunction "8_8") (pintype "passive"))
    )
    (net (code "66") (name "unconnected-(P4-Pad9)") (class "Default")
      (node (ref "P4") (pin "9") (pinfunction "9_9") (pintype "passive"))
    )
    (net (code "67") (name "unconnected-(P4-Pad10)") (class "Default")
      (node (ref "P4") (pin "10") (pinfunction "10_10") (pintype "passive"))
    )
    (net (code "68") (name "unconnected-(U9-NC-Pad23)") (class "Default")
      (node (ref "U9") (pin "23") (pinfunction "NC_23") (pintype "passive"))
    )
    (net (code "69") (name "unconnected-(U12-NC-Pad23)") (class "Default")
      (node (ref "U12") (pin "23") (pinfunction "NC_23") (pintype "passive"))
    )
    (net (code "70") (name "unconnected-(U12-Y4-Pad11)") (class "Default")
      (node (ref "U12") (pin "11") (pinfunction "Y4_11") (pintype "passive+no_connect"))
    )
    (net (code "71") (name "unconnected-(U13-PAD-Pad9)") (class "Default")
      (node (ref "U13") (pin "9") (pinfunction "PAD_9") (pintype "passive+no_connect"))
    )
    (net (code "72") (name "unconnected-(U14-NC-Pad23)") (class "Default")
      (node (ref "U14") (pin "23") (pinfunction "NC_23") (pintype "passive"))
    )
  )
)
